# atxmega_e5.net
KiCad netlist of a schematic drawn in EAGLE
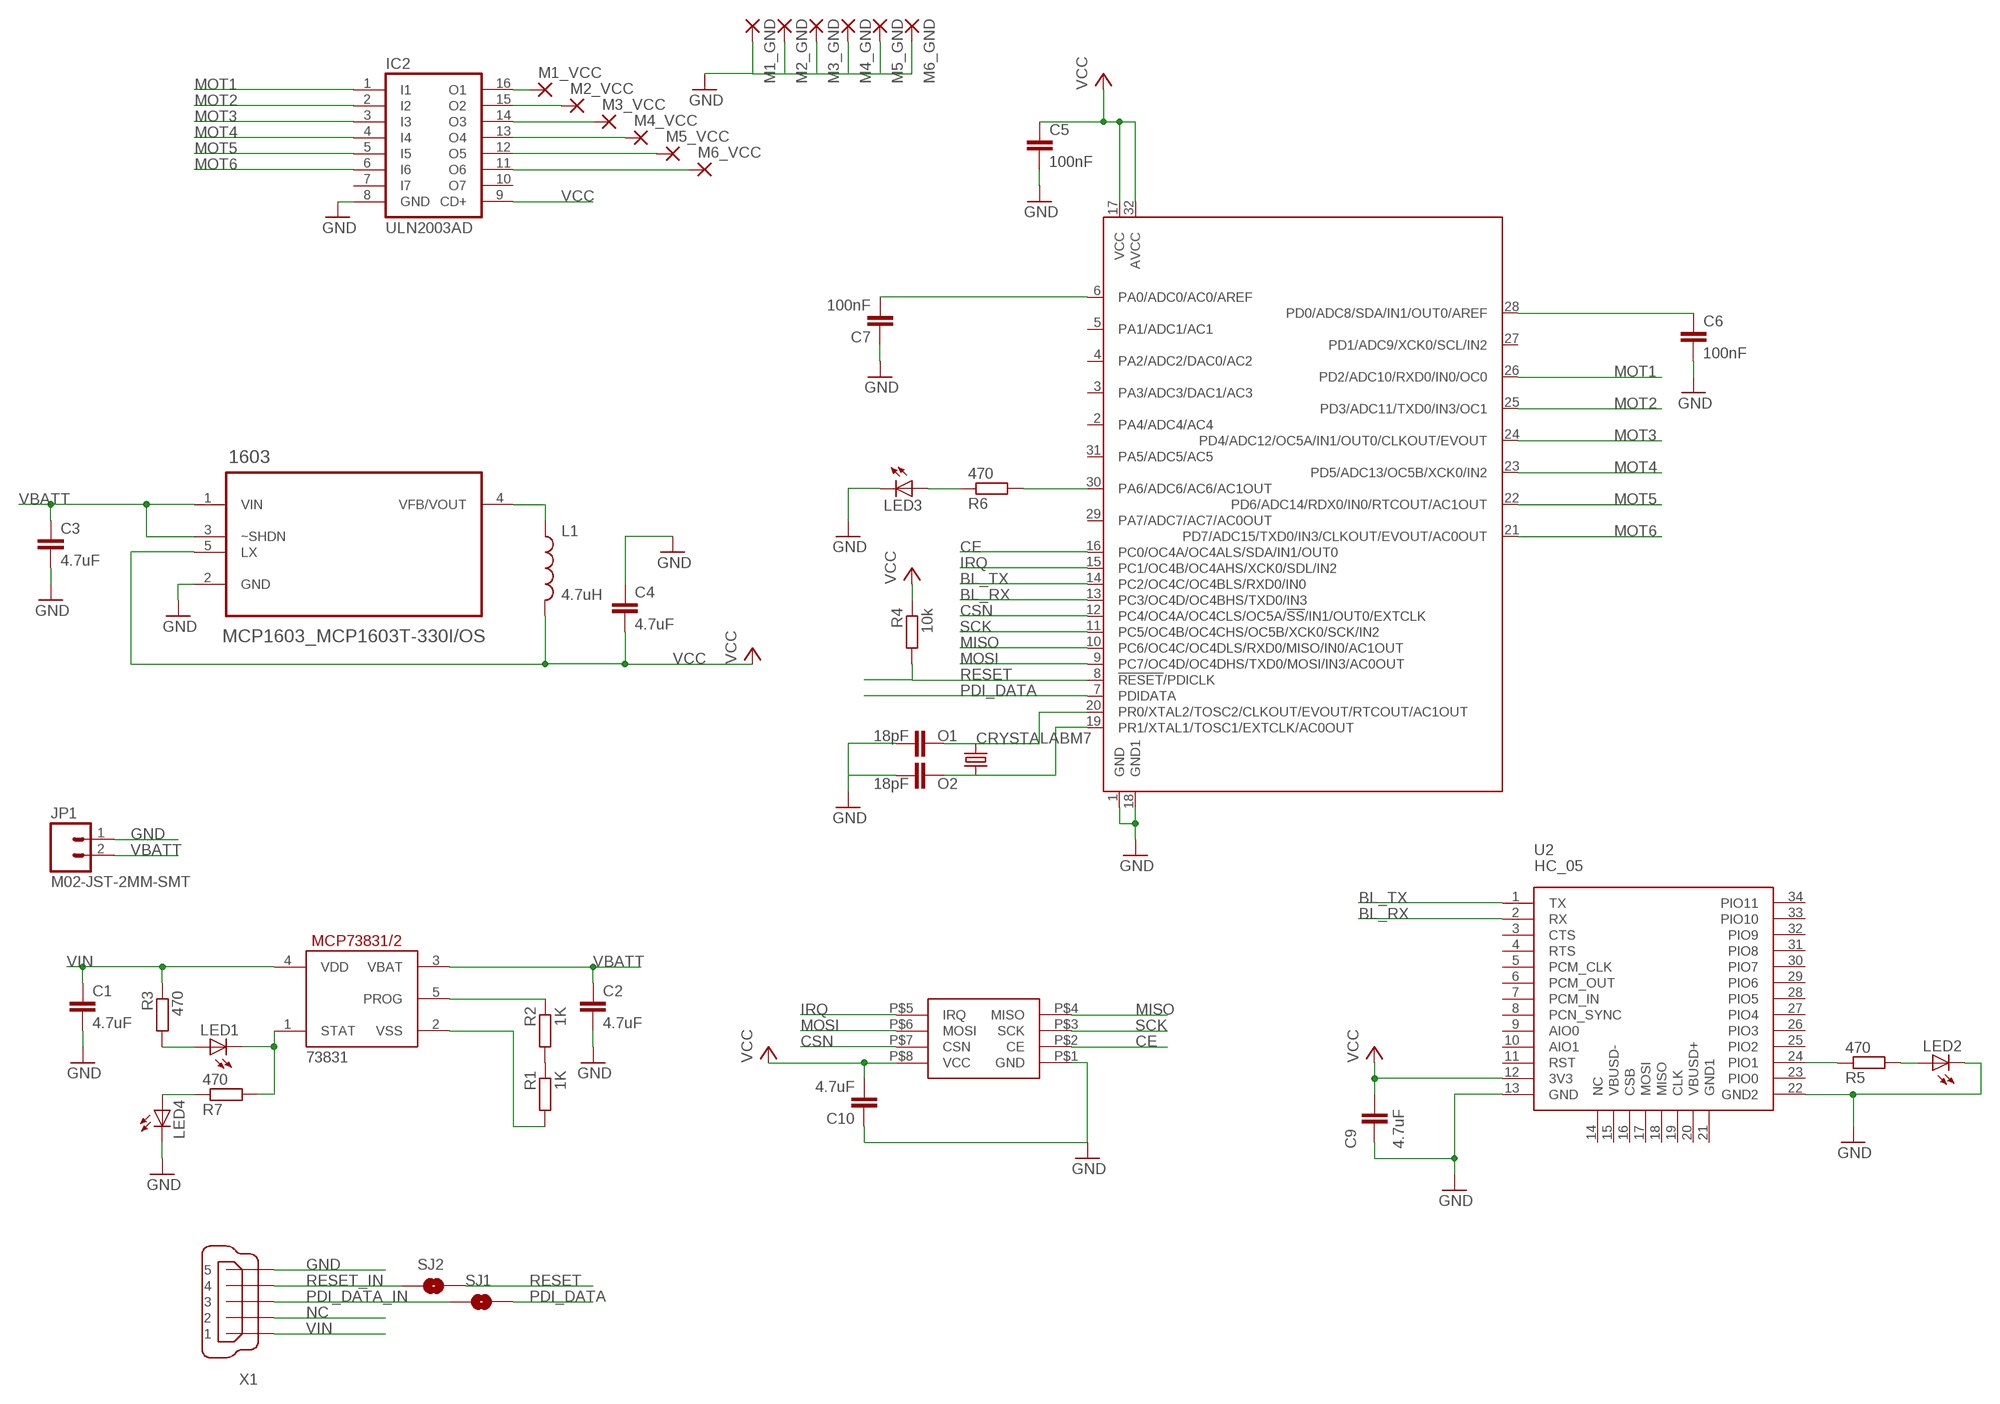
[diagram p0: schematic, sheet 1]

(export (version "E")
  (design (tool "Eeschema 10.0.6"))
  (components
    (comp (ref "1603")
      (value "MCP1603_MCP1603T-330I/OS")
      (footprint "eagle-import:MCP1603_SOT95P280X110-5N")
      (fields (field (name "MPN") "MCP1603T-330I/OS"))
      (libsource (lib "eagle-import") (part "MCP1603_MCP1603T-330I/OS"))
    )
    (comp (ref "73831")
      (value "MCP73831/OT")
      (footprint "eagle-import:SOT23-5L")
      (libsource (lib "eagle-import") (part "MCP73831/OT"))
    )
    (comp (ref "C1")
      (value "4.7uF")
      (footprint "eagle-import:C0603K")
      (libsource (lib "eagle-import") (part "C-EUC0603K"))
    )
    (comp (ref "C2")
      (value "4.7uF")
      (footprint "eagle-import:C0603K")
      (libsource (lib "eagle-import") (part "C-EUC0603K"))
    )
    (comp (ref "C3")
      (value "4.7uF")
      (footprint "eagle-import:C0603K")
      (libsource (lib "eagle-import") (part "C-EUC0603K"))
    )
    (comp (ref "C4")
      (value "4.7uF")
      (footprint "eagle-import:C0603K")
      (libsource (lib "eagle-import") (part "C-EUC0603K"))
    )
    (comp (ref "C5")
      (value "100nF")
      (footprint "eagle-import:C0603K")
      (libsource (lib "eagle-import") (part "C-EUC0603K"))
    )
    (comp (ref "C6")
      (value "100nF")
      (footprint "eagle-import:C0603K")
      (libsource (lib "eagle-import") (part "C-EUC0603K"))
    )
    (comp (ref "C7")
      (value "100nF")
      (footprint "eagle-import:C0603K")
      (libsource (lib "eagle-import") (part "C-EUC0603K"))
    )
    (comp (ref "C9")
      (value "4.7uF")
      (footprint "eagle-import:C0603K")
      (libsource (lib "eagle-import") (part "C-EUC0603K"))
    )
    (comp (ref "C10")
      (value "4.7uF")
      (footprint "eagle-import:C0603K")
      (libsource (lib "eagle-import") (part "C-EUC0603K"))
    )
    (comp (ref "IC2")
      (value "ULN2003AD")
      (footprint "eagle-import:SO16")
      (libsource (lib "eagle-import") (part "ULN2003AD"))
    )
    (comp (ref "JP1")
      (value "M02-JST-2MM-SMT")
      (footprint "eagle-import:JST-2-SMD")
      (libsource (lib "eagle-import") (part "M02-JST-2MM-SMT"))
    )
    (comp (ref "L1")
      (value "4.7uH")
      (footprint "eagle-import:1007")
      (libsource (lib "eagle-import") (part "INDUCTOR1007"))
    )
    (comp (ref "LED1")
      (value "LED0805LED")
      (footprint "eagle-import:0805LED")
      (libsource (lib "eagle-import") (part "LED0805LED"))
    )
    (comp (ref "LED2")
      (value "LED0805LED")
      (footprint "eagle-import:0805LED")
      (libsource (lib "eagle-import") (part "LED0805LED"))
    )
    (comp (ref "LED3")
      (value "LED0805LED")
      (footprint "eagle-import:0805LED")
      (libsource (lib "eagle-import") (part "LED0805LED"))
    )
    (comp (ref "LED4")
      (value "LED0805LED")
      (footprint "eagle-import:0805LED")
      (libsource (lib "eagle-import") (part "LED0805LED"))
    )
    (comp (ref "M1_GND")
      (value "WIREPAD2,15/1,0")
      (footprint "eagle-import:2,15_1,0")
      (libsource (lib "eagle-import") (part "WIREPAD2,15/1,0"))
    )
    (comp (ref "M1_VCC")
      (value "WIREPAD2,15/1,0")
      (footprint "eagle-import:2,15_1,0")
      (libsource (lib "eagle-import") (part "WIREPAD2,15/1,0"))
    )
    (comp (ref "M2_GND")
      (value "WIREPAD2,15/1,0")
      (footprint "eagle-import:2,15_1,0")
      (libsource (lib "eagle-import") (part "WIREPAD2,15/1,0"))
    )
    (comp (ref "M2_VCC")
      (value "WIREPAD2,15/1,0")
      (footprint "eagle-import:2,15_1,0")
      (libsource (lib "eagle-import") (part "WIREPAD2,15/1,0"))
    )
    (comp (ref "M3_GND")
      (value "WIREPAD2,15/1,0")
      (footprint "eagle-import:2,15_1,0")
      (libsource (lib "eagle-import") (part "WIREPAD2,15/1,0"))
    )
    (comp (ref "M3_VCC")
      (value "WIREPAD2,15/1,0")
      (footprint "eagle-import:2,15_1,0")
      (libsource (lib "eagle-import") (part "WIREPAD2,15/1,0"))
    )
    (comp (ref "M4_GND")
      (value "WIREPAD2,15/1,0")
      (footprint "eagle-import:2,15_1,0")
      (libsource (lib "eagle-import") (part "WIREPAD2,15/1,0"))
    )
    (comp (ref "M4_VCC")
      (value "WIREPAD2,15/1,0")
      (footprint "eagle-import:2,15_1,0")
      (libsource (lib "eagle-import") (part "WIREPAD2,15/1,0"))
    )
    (comp (ref "M5_GND")
      (value "WIREPAD2,15/1,0")
      (footprint "eagle-import:2,15_1,0")
      (libsource (lib "eagle-import") (part "WIREPAD2,15/1,0"))
    )
    (comp (ref "M5_VCC")
      (value "WIREPAD2,15/1,0")
      (footprint "eagle-import:2,15_1,0")
      (libsource (lib "eagle-import") (part "WIREPAD2,15/1,0"))
    )
    (comp (ref "M6_GND")
      (value "WIREPAD2,15/1,0")
      (footprint "eagle-import:2,15_1,0")
      (libsource (lib "eagle-import") (part "WIREPAD2,15/1,0"))
    )
    (comp (ref "M6_VCC")
      (value "WIREPAD2,15/1,0")
      (footprint "eagle-import:2,15_1,0")
      (libsource (lib "eagle-import") (part "WIREPAD2,15/1,0"))
    )
    (comp (ref "O1")
      (value "18pF")
      (footprint "eagle-import:C0603K")
      (libsource (lib "eagle-import") (part "C-EUC0603K"))
    )
    (comp (ref "O2")
      (value "18pF")
      (footprint "eagle-import:C0603K")
      (libsource (lib "eagle-import") (part "C-EUC0603K"))
    )
    (comp (ref "R1")
      (value "1K")
      (footprint "eagle-import:R0603")
      (libsource (lib "eagle-import") (part "R-EU_R0603"))
    )
    (comp (ref "R2")
      (value "1K")
      (footprint "eagle-import:R0603")
      (libsource (lib "eagle-import") (part "R-EU_R0603"))
    )
    (comp (ref "R3")
      (value "470")
      (footprint "eagle-import:R0603")
      (libsource (lib "eagle-import") (part "R-EU_R0603"))
    )
    (comp (ref "R4")
      (value "10k")
      (footprint "eagle-import:R0603")
      (libsource (lib "eagle-import") (part "R-EU_R0603"))
    )
    (comp (ref "R5")
      (value "470")
      (footprint "eagle-import:R0603")
      (libsource (lib "eagle-import") (part "R-EU_R0603"))
    )
    (comp (ref "R6")
      (value "470")
      (footprint "eagle-import:R0603")
      (libsource (lib "eagle-import") (part "R-EU_R0603"))
    )
    (comp (ref "R7")
      (value "470")
      (footprint "eagle-import:R0603")
      (libsource (lib "eagle-import") (part "R-EU_R0603"))
    )
    (comp (ref "SJ1")
      (value "SOLDERJUMPERNO")
      (footprint "eagle-import:SJ_2S-NO")
      (libsource (lib "eagle-import") (part "SOLDERJUMPERNO"))
    )
    (comp (ref "SJ2")
      (value "SOLDERJUMPERNO")
      (footprint "eagle-import:SJ_2S-NO")
      (libsource (lib "eagle-import") (part "SOLDERJUMPERNO"))
    )
    (comp (ref "U$1")
      (value "CRYSTALABM7")
      (footprint "eagle-import:ABM7")
      (libsource (lib "eagle-import") (part "CRYSTALABM7"))
    )
    (comp (ref "U$2")
      (value "NRF24L01+")
      (footprint "eagle-import:NRF24L01+")
      (libsource (lib "eagle-import") (part "NRF24L01+"))
    )
    (comp (ref "U1")
      (value "ATXMEGAE5AU")
      (footprint "eagle-import:TQFP32")
      (libsource (lib "eagle-import") (part "ATXMEGAE5AU"))
    )
    (comp (ref "U2")
      (value "HC_05")
      (footprint "eagle-import:BLUETOOTH_SMD")
      (libsource (lib "eagle-import") (part "HC_05"))
    )
    (comp (ref "X1")
      (value "MINI-USB-32005-201")
      (footprint "eagle-import:32005-201")
      (libsource (lib "eagle-import") (part "MINI-USB-32005-201"))
    )
  )
  (nets
    (net (code "1") (name "/BL_RX") (class "Default")
      (node (ref "U1") (pin "13") (pinfunction "PC3/OC4D/OC4BHS/TXD0/IN3_13") (pintype "bidirectional"))
      (node (ref "U2") (pin "2") (pinfunction "RX_2") (pintype "bidirectional"))
    )
    (net (code "2") (name "/BL_TX") (class "Default")
      (node (ref "U1") (pin "14") (pinfunction "PC2/OC4C/OC4BLS/RXD0/IN0_14") (pintype "bidirectional"))
      (node (ref "U2") (pin "1") (pinfunction "TX_1") (pintype "bidirectional"))
    )
    (net (code "3") (name "/CE") (class "Default")
      (node (ref "U$2") (pin "P$2") (pinfunction "CE_P$2") (pintype "bidirectional"))
      (node (ref "U1") (pin "16") (pinfunction "PC0/OC4A/OC4ALS/SDA/IN1/OUT0_16") (pintype "bidirectional"))
    )
    (net (code "4") (name "/CSN") (class "Default")
      (node (ref "U$2") (pin "P$7") (pinfunction "CSN_P$7") (pintype "bidirectional"))
      (node (ref "U1") (pin "12") (pinfunction "PC4/OC4A/OC4CLS/OC5A/~{SS}/IN1/OUT0/EXTCLK_12") (pintype "bidirectional"))
    )
    (net (code "5") (name "/IRQ") (class "Default")
      (node (ref "U$2") (pin "P$5") (pinfunction "IRQ_P$5") (pintype "bidirectional"))
      (node (ref "U1") (pin "15") (pinfunction "PC1/OC4B/OC4AHS/XCK0/SDL/IN2_15") (pintype "bidirectional"))
    )
    (net (code "6") (name "/MISO") (class "Default")
      (node (ref "U$2") (pin "P$4") (pinfunction "MISO_P$4") (pintype "bidirectional"))
      (node (ref "U1") (pin "10") (pinfunction "PC6/OC4C/OC4DLS/RXD0/MISO/IN0/AC1OUT_10") (pintype "bidirectional"))
    )
    (net (code "7") (name "/MOSI") (class "Default")
      (node (ref "U$2") (pin "P$6") (pinfunction "MOSI_P$6") (pintype "bidirectional"))
      (node (ref "U1") (pin "9") (pinfunction "PC7/OC4D/OC4DHS/TXD0/MOSI/IN3/AC0OUT_9") (pintype "bidirectional"))
    )
    (net (code "8") (name "/MOT1") (class "Default")
      (node (ref "IC2") (pin "1") (pinfunction "I1_1") (pintype "input"))
      (node (ref "U1") (pin "26") (pinfunction "PD2/ADC10/RXD0/IN0/OC0_26") (pintype "bidirectional"))
    )
    (net (code "9") (name "/MOT2") (class "Default")
      (node (ref "IC2") (pin "2") (pinfunction "I2_2") (pintype "input"))
      (node (ref "U1") (pin "25") (pinfunction "PD3/ADC11/TXD0/IN3/OC1_25") (pintype "bidirectional"))
    )
    (net (code "10") (name "/MOT3") (class "Default")
      (node (ref "IC2") (pin "3") (pinfunction "I3_3") (pintype "input"))
      (node (ref "U1") (pin "24") (pinfunction "PD4/ADC12/OC5A/IN1/OUT0/CLKOUT/EVOUT_24") (pintype "bidirectional"))
    )
    (net (code "11") (name "/MOT4") (class "Default")
      (node (ref "IC2") (pin "4") (pinfunction "I4_4") (pintype "input"))
      (node (ref "U1") (pin "23") (pinfunction "PD5/ADC13/OC5B/XCK0/IN2_23") (pintype "bidirectional"))
    )
    (net (code "12") (name "/MOT5") (class "Default")
      (node (ref "IC2") (pin "5") (pinfunction "I5_5") (pintype "input"))
      (node (ref "U1") (pin "22") (pinfunction "PD6/ADC14/RDX0/IN0/RTCOUT/AC1OUT_22") (pintype "bidirectional"))
    )
    (net (code "13") (name "/MOT6") (class "Default")
      (node (ref "IC2") (pin "6") (pinfunction "I6_6") (pintype "input"))
      (node (ref "U1") (pin "21") (pinfunction "PD7/ADC15/TXD0/IN3/CLKOUT/EVOUT/AC0OUT_21") (pintype "bidirectional"))
    )
    (net (code "14") (name "/NC") (class "Default")
      (node (ref "X1") (pin "2") (pinfunction "2_2") (pintype "passive"))
    )
    (net (code "15") (name "/PDI_DATA") (class "Default")
      (node (ref "SJ1") (pin "2") (pinfunction "2_2") (pintype "passive"))
      (node (ref "U1") (pin "7") (pinfunction "PDIDATA_7") (pintype "bidirectional"))
    )
    (net (code "16") (name "/PDI_DATA_IN") (class "Default")
      (node (ref "SJ1") (pin "1") (pinfunction "1_1") (pintype "passive"))
      (node (ref "X1") (pin "3") (pinfunction "3_3") (pintype "passive"))
    )
    (net (code "17") (name "/RESET") (class "Default")
      (node (ref "R4") (pin "2") (pinfunction "2_2") (pintype "passive"))
      (node (ref "SJ2") (pin "2") (pinfunction "2_2") (pintype "passive"))
      (node (ref "U1") (pin "8") (pinfunction "~{RESET}/PDICLK_8") (pintype "bidirectional"))
    )
    (net (code "18") (name "/RESET_IN") (class "Default")
      (node (ref "SJ2") (pin "1") (pinfunction "1_1") (pintype "passive"))
      (node (ref "X1") (pin "4") (pinfunction "4_4") (pintype "passive"))
    )
    (net (code "19") (name "/SCK") (class "Default")
      (node (ref "U$2") (pin "P$3") (pinfunction "SCK_P$3") (pintype "bidirectional"))
      (node (ref "U1") (pin "11") (pinfunction "PC5/OC4B/OC4CHS/OC5B/XCK0/SCK/IN2_11") (pintype "bidirectional"))
    )
    (net (code "20") (name "/VBATT") (class "Default")
      (node (ref "1603") (pin "1") (pinfunction "VIN_1") (pintype "power_in"))
      (node (ref "1603") (pin "3") (pinfunction "~{SHDN}_3") (pintype "input"))
      (node (ref "73831") (pin "3") (pinfunction "VBAT_3") (pintype "bidirectional"))
      (node (ref "C2") (pin "1") (pinfunction "1_1") (pintype "passive"))
      (node (ref "C3") (pin "1") (pinfunction "1_1") (pintype "passive"))
      (node (ref "JP1") (pin "2") (pinfunction "1_2") (pintype "passive"))
    )
    (net (code "21") (name "/VIN") (class "Default")
      (node (ref "73831") (pin "4") (pinfunction "VDD_4") (pintype "power_in"))
      (node (ref "C1") (pin "1") (pinfunction "1_1") (pintype "passive"))
      (node (ref "R3") (pin "1") (pinfunction "1_1") (pintype "passive"))
      (node (ref "X1") (pin "1") (pinfunction "1_1") (pintype "passive"))
    )
    (net (code "22") (name "GND") (class "Default")
      (node (ref "1603") (pin "2") (pinfunction "GND_2") (pintype "passive"))
      (node (ref "C1") (pin "2") (pinfunction "2_2") (pintype "passive"))
      (node (ref "C10") (pin "1") (pinfunction "1_1") (pintype "passive"))
      (node (ref "C2") (pin "2") (pinfunction "2_2") (pintype "passive"))
      (node (ref "C3") (pin "2") (pinfunction "2_2") (pintype "passive"))
      (node (ref "C4") (pin "1") (pinfunction "1_1") (pintype "passive"))
      (node (ref "C5") (pin "2") (pinfunction "2_2") (pintype "passive"))
      (node (ref "C6") (pin "2") (pinfunction "2_2") (pintype "passive"))
      (node (ref "C7") (pin "1") (pinfunction "1_1") (pintype "passive"))
      (node (ref "C9") (pin "2") (pinfunction "2_2") (pintype "passive"))
      (node (ref "IC2") (pin "8") (pinfunction "GND_8") (pintype "power_in"))
      (node (ref "JP1") (pin "1") (pinfunction "2_1") (pintype "passive"))
      (node (ref "LED2") (pin "C") (pinfunction "C_C") (pintype "passive"))
      (node (ref "LED3") (pin "C") (pinfunction "C_C") (pintype "passive"))
      (node (ref "LED4") (pin "C") (pinfunction "C_C") (pintype "passive"))
      (node (ref "M1_GND") (pin "1") (pinfunction "P_1") (pintype "passive"))
      (node (ref "M2_GND") (pin "1") (pinfunction "P_1") (pintype "passive"))
      (node (ref "M3_GND") (pin "1") (pinfunction "P_1") (pintype "passive"))
      (node (ref "M4_GND") (pin "1") (pinfunction "P_1") (pintype "passive"))
      (node (ref "M5_GND") (pin "1") (pinfunction "P_1") (pintype "passive"))
      (node (ref "M6_GND") (pin "1") (pinfunction "P_1") (pintype "passive"))
      (node (ref "O1") (pin "2") (pinfunction "2_2") (pintype "passive"))
      (node (ref "O2") (pin "2") (pinfunction "2_2") (pintype "passive"))
      (node (ref "U$2") (pin "P$1") (pinfunction "GND_P$1") (pintype "power_in"))
      (node (ref "U1") (pin "1") (pinfunction "GND_1") (pintype "bidirectional"))
      (node (ref "U1") (pin "18") (pinfunction "GND1_18") (pintype "bidirectional"))
      (node (ref "U2") (pin "13") (pinfunction "GND_13") (pintype "bidirectional"))
      (node (ref "U2") (pin "22") (pinfunction "GND2_22") (pintype "bidirectional"))
      (node (ref "X1") (pin "5") (pinfunction "5_5") (pintype "passive"))
    )
    (net (code "23") (name "Net-(1603-VFB{slash}VOUT)") (class "Default")
      (node (ref "1603") (pin "4") (pinfunction "VFB/VOUT_4") (pintype "output"))
      (node (ref "L1") (pin "1") (pinfunction "1_1") (pintype "passive"))
    )
    (net (code "24") (name "Net-(73831-PROG)") (class "Default")
      (node (ref "73831") (pin "5") (pinfunction "PROG_5") (pintype "input"))
      (node (ref "R2") (pin "1") (pinfunction "1_1") (pintype "passive"))
    )
    (net (code "25") (name "Net-(73831-STAT)") (class "Default")
      (node (ref "73831") (pin "1") (pinfunction "STAT_1") (pintype "output"))
      (node (ref "LED1") (pin "C") (pinfunction "C_C") (pintype "passive"))
      (node (ref "R7") (pin "2") (pinfunction "2_2") (pintype "passive"))
    )
    (net (code "26") (name "Net-(73831-VSS)") (class "Default")
      (node (ref "73831") (pin "2") (pinfunction "VSS_2") (pintype "power_in"))
      (node (ref "R1") (pin "2") (pinfunction "2_2") (pintype "passive"))
    )
    (net (code "27") (name "Net-(IC2-O1)") (class "Default")
      (node (ref "IC2") (pin "16") (pinfunction "O1_16") (pintype "open_collector"))
      (node (ref "M1_VCC") (pin "1") (pinfunction "P_1") (pintype "passive"))
    )
    (net (code "28") (name "Net-(IC2-O2)") (class "Default")
      (node (ref "IC2") (pin "15") (pinfunction "O2_15") (pintype "open_collector"))
      (node (ref "M2_VCC") (pin "1") (pinfunction "P_1") (pintype "passive"))
    )
    (net (code "29") (name "Net-(IC2-O3)") (class "Default")
      (node (ref "IC2") (pin "14") (pinfunction "O3_14") (pintype "open_collector"))
      (node (ref "M3_VCC") (pin "1") (pinfunction "P_1") (pintype "passive"))
    )
    (net (code "30") (name "Net-(IC2-O4)") (class "Default")
      (node (ref "IC2") (pin "13") (pinfunction "O4_13") (pintype "open_collector"))
      (node (ref "M4_VCC") (pin "1") (pinfunction "P_1") (pintype "passive"))
    )
    (net (code "31") (name "Net-(IC2-O5)") (class "Default")
      (node (ref "IC2") (pin "12") (pinfunction "O5_12") (pintype "open_collector"))
      (node (ref "M5_VCC") (pin "1") (pinfunction "P_1") (pintype "passive"))
    )
    (net (code "32") (name "Net-(IC2-O6)") (class "Default")
      (node (ref "IC2") (pin "11") (pinfunction "O6_11") (pintype "open_collector"))
      (node (ref "M6_VCC") (pin "1") (pinfunction "P_1") (pintype "passive"))
    )
    (net (code "33") (name "Net-(LED1-PadA)") (class "Default")
      (node (ref "LED1") (pin "A") (pinfunction "A_A") (pintype "passive"))
      (node (ref "R3") (pin "2") (pinfunction "2_2") (pintype "passive"))
    )
    (net (code "34") (name "Net-(LED2-PadA)") (class "Default")
      (node (ref "LED2") (pin "A") (pinfunction "A_A") (pintype "passive"))
      (node (ref "R5") (pin "2") (pinfunction "2_2") (pintype "passive"))
    )
    (net (code "35") (name "Net-(LED3-PadA)") (class "Default")
      (node (ref "LED3") (pin "A") (pinfunction "A_A") (pintype "passive"))
      (node (ref "R6") (pin "1") (pinfunction "1_1") (pintype "passive"))
    )
    (net (code "36") (name "Net-(LED4-PadA)") (class "Default")
      (node (ref "LED4") (pin "A") (pinfunction "A_A") (pintype "passive"))
      (node (ref "R7") (pin "1") (pinfunction "1_1") (pintype "passive"))
    )
    (net (code "37") (name "Net-(R1-Pad1)") (class "Default")
      (node (ref "R1") (pin "1") (pinfunction "1_1") (pintype "passive"))
      (node (ref "R2") (pin "2") (pinfunction "2_2") (pintype "passive"))
    )
    (net (code "38") (name "Net-(U$1-1)") (class "Default")
      (node (ref "O2") (pin "1") (pinfunction "1_1") (pintype "passive"))
      (node (ref "U$1") (pin "P$1") (pinfunction "1_P$1") (pintype "passive"))
      (node (ref "U1") (pin "19") (pinfunction "PR1/XTAL1/TOSC1/EXTCLK/AC0OUT_19") (pintype "bidirectional"))
    )
    (net (code "39") (name "Net-(U$1-2)") (class "Default")
      (node (ref "O1") (pin "1") (pinfunction "1_1") (pintype "passive"))
      (node (ref "U$1") (pin "P$2") (pinfunction "2_P$2") (pintype "passive"))
      (node (ref "U1") (pin "20") (pinfunction "PR0/XTAL2/TOSC2/CLKOUT/EVOUT/RTCOUT/AC1OUT_20") (pintype "bidirectional"))
    )
    (net (code "40") (name "Net-(U1-PA0{slash}ADC0{slash}AC0{slash}AREF)") (class "Default")
      (node (ref "C7") (pin "2") (pinfunction "2_2") (pintype "passive"))
      (node (ref "U1") (pin "6") (pinfunction "PA0/ADC0/AC0/AREF_6") (pintype "bidirectional"))
    )
    (net (code "41") (name "Net-(U1-PA6{slash}ADC6{slash}AC6{slash}AC1OUT)") (class "Default")
      (node (ref "R6") (pin "2") (pinfunction "2_2") (pintype "passive"))
      (node (ref "U1") (pin "30") (pinfunction "PA6/ADC6/AC6/AC1OUT_30") (pintype "bidirectional"))
    )
    (net (code "42") (name "Net-(U1-PD0{slash}ADC8{slash}SDA{slash}IN1{slash}OUT0{slash}AREF)") (class "Default")
      (node (ref "C6") (pin "1") (pinfunction "1_1") (pintype "passive"))
      (node (ref "U1") (pin "28") (pinfunction "PD0/ADC8/SDA/IN1/OUT0/AREF_28") (pintype "bidirectional"))
    )
    (net (code "43") (name "Net-(U2-PIO1)") (class "Default")
      (node (ref "R5") (pin "1") (pinfunction "1_1") (pintype "passive"))
      (node (ref "U2") (pin "24") (pinfunction "PIO1_24") (pintype "bidirectional"))
    )
    (net (code "44") (name "VCC") (class "Default")
      (node (ref "1603") (pin "5") (pinfunction "LX_5") (pintype "input"))
      (node (ref "C10") (pin "2") (pinfunction "2_2") (pintype "passive"))
      (node (ref "C4") (pin "2") (pinfunction "2_2") (pintype "passive"))
      (node (ref "C5") (pin "1") (pinfunction "1_1") (pintype "passive"))
      (node (ref "C9") (pin "1") (pinfunction "1_1") (pintype "passive"))
      (node (ref "IC2") (pin "9") (pinfunction "CD+_9") (pintype "passive"))
      (node (ref "L1") (pin "2") (pinfunction "2_2") (pintype "passive"))
      (node (ref "R4") (pin "1") (pinfunction "1_1") (pintype "passive"))
      (node (ref "U$2") (pin "P$8") (pinfunction "VCC_P$8") (pintype "power_in"))
      (node (ref "U1") (pin "17") (pinfunction "VCC_17") (pintype "bidirectional"))
      (node (ref "U1") (pin "32") (pinfunction "AVCC_32") (pintype "bidirectional"))
      (node (ref "U2") (pin "12") (pinfunction "3V3_12") (pintype "bidirectional"))
    )
    (net (code "45") (name "unconnected-(IC2-I7-Pad7)") (class "Default")
      (node (ref "IC2") (pin "7") (pinfunction "I7_7") (pintype "input"))
    )
    (net (code "46") (name "unconnected-(IC2-O7-Pad10)") (class "Default")
      (node (ref "IC2") (pin "10") (pinfunction "O7_10") (pintype "open_collector"))
    )
    (net (code "47") (name "unconnected-(U1-PA1{slash}ADC1{slash}AC1-Pad5)") (class "Default")
      (node (ref "U1") (pin "5") (pinfunction "PA1/ADC1/AC1_5") (pintype "bidirectional"))
    )
    (net (code "48") (name "unconnected-(U1-PA2{slash}ADC2{slash}DAC0{slash}AC2-Pad4)") (class "Default")
      (node (ref "U1") (pin "4") (pinfunction "PA2/ADC2/DAC0/AC2_4") (pintype "bidirectional"))
    )
    (net (code "49") (name "unconnected-(U1-PA3{slash}ADC3{slash}DAC1{slash}AC3-Pad3)") (class "Default")
      (node (ref "U1") (pin "3") (pinfunction "PA3/ADC3/DAC1/AC3_3") (pintype "bidirectional"))
    )
    (net (code "50") (name "unconnected-(U1-PA4{slash}ADC4{slash}AC4-Pad2)") (class "Default")
      (node (ref "U1") (pin "2") (pinfunction "PA4/ADC4/AC4_2") (pintype "bidirectional"))
    )
    (net (code "51") (name "unconnected-(U1-PA5{slash}ADC5{slash}AC5-Pad31)") (class "Default")
      (node (ref "U1") (pin "31") (pinfunction "PA5/ADC5/AC5_31") (pintype "bidirectional"))
    )
    (net (code "52") (name "unconnected-(U1-PA7{slash}ADC7{slash}AC7{slash}AC0OUT-Pad29)") (class "Default")
      (node (ref "U1") (pin "29") (pinfunction "PA7/ADC7/AC7/AC0OUT_29") (pintype "bidirectional"))
    )
    (net (code "53") (name "unconnected-(U1-PD1{slash}ADC9{slash}XCK0{slash}SCL{slash}IN2-Pad27)") (class "Default")
      (node (ref "U1") (pin "27") (pinfunction "PD1/ADC9/XCK0/SCL/IN2_27") (pintype "bidirectional"))
    )
    (net (code "54") (name "unconnected-(U2-AIO0-Pad9)") (class "Default")
      (node (ref "U2") (pin "9") (pinfunction "AIO0_9") (pintype "bidirectional"))
    )
    (net (code "55") (name "unconnected-(U2-AIO1-Pad10)") (class "Default")
      (node (ref "U2") (pin "10") (pinfunction "AIO1_10") (pintype "bidirectional"))
    )
    (net (code "56") (name "unconnected-(U2-CLK-Pad19)") (class "Default")
      (node (ref "U2") (pin "19") (pinfunction "CLK_19") (pintype "bidirectional"))
    )
    (net (code "57") (name "unconnected-(U2-CSB-Pad16)") (class "Default")
      (node (ref "U2") (pin "16") (pinfunction "CSB_16") (pintype "bidirectional"))
    )
    (net (code "58") (name "unconnected-(U2-CTS-Pad3)") (class "Default")
      (node (ref "U2") (pin "3") (pinfunction "CTS_3") (pintype "bidirectional"))
    )
    (net (code "59") (name "unconnected-(U2-GND1-Pad21)") (class "Default")
      (node (ref "U2") (pin "21") (pinfunction "GND1_21") (pintype "bidirectional"))
    )
    (net (code "60") (name "unconnected-(U2-MISO-Pad18)") (class "Default")
      (node (ref "U2") (pin "18") (pinfunction "MISO_18") (pintype "bidirectional"))
    )
    (net (code "61") (name "unconnected-(U2-MOSI-Pad17)") (class "Default")
      (node (ref "U2") (pin "17") (pinfunction "MOSI_17") (pintype "bidirectional"))
    )
    (net (code "62") (name "unconnected-(U2-NC-Pad14)") (class "Default")
      (node (ref "U2") (pin "14") (pinfunction "NC_14") (pintype "bidirectional"))
    )
    (net (code "63") (name "unconnected-(U2-PCM_CLK-Pad5)") (class "Default")
      (node (ref "U2") (pin "5") (pinfunction "PCM_CLK_5") (pintype "bidirectional"))
    )
    (net (code "64") (name "unconnected-(U2-PCM_IN-Pad7)") (class "Default")
      (node (ref "U2") (pin "7") (pinfunction "PCM_IN_7") (pintype "bidirectional"))
    )
    (net (code "65") (name "unconnected-(U2-PCM_OUT-Pad6)") (class "Default")
      (node (ref "U2") (pin "6") (pinfunction "PCM_OUT_6") (pintype "bidirectional"))
    )
    (net (code "66") (name "unconnected-(U2-PCN_SYNC-Pad8)") (class "Default")
      (node (ref "U2") (pin "8") (pinfunction "PCN_SYNC_8") (pintype "bidirectional"))
    )
    (net (code "67") (name "unconnected-(U2-PIO0-Pad23)") (class "Default")
      (node (ref "U2") (pin "23") (pinfunction "PIO0_23") (pintype "bidirectional"))
    )
    (net (code "68") (name "unconnected-(U2-PIO2-Pad25)") (class "Default")
      (node (ref "U2") (pin "25") (pinfunction "PIO2_25") (pintype "bidirectional"))
    )
    (net (code "69") (name "unconnected-(U2-PIO3-Pad26)") (class "Default")
      (node (ref "U2") (pin "26") (pinfunction "PIO3_26") (pintype "bidirectional"))
    )
    (net (code "70") (name "unconnected-(U2-PIO4-Pad27)") (class "Default")
      (node (ref "U2") (pin "27") (pinfunction "PIO4_27") (pintype "bidirectional"))
    )
    (net (code "71") (name "unconnected-(U2-PIO5-Pad28)") (class "Default")
      (node (ref "U2") (pin "28") (pinfunction "PIO5_28") (pintype "bidirectional"))
    )
    (net (code "72") (name "unconnected-(U2-PIO6-Pad29)") (class "Default")
      (node (ref "U2") (pin "29") (pinfunction "PIO6_29") (pintype "bidirectional"))
    )
    (net (code "73") (name "unconnected-(U2-PIO7-Pad30)") (class "Default")
      (node (ref "U2") (pin "30") (pinfunction "PIO7_30") (pintype "bidirectional"))
    )
    (net (code "74") (name "unconnected-(U2-PIO8-Pad31)") (class "Default")
      (node (ref "U2") (pin "31") (pinfunction "PIO8_31") (pintype "bidirectional"))
    )
    (net (code "75") (name "unconnected-(U2-PIO9-Pad32)") (class "Default")
      (node (ref "U2") (pin "32") (pinfunction "PIO9_32") (pintype "bidirectional"))
    )
    (net (code "76") (name "unconnected-(U2-PIO10-Pad33)") (class "Default")
      (node (ref "U2") (pin "33") (pinfunction "PIO10_33") (pintype "bidirectional"))
    )
    (net (code "77") (name "unconnected-(U2-PIO11-Pad34)") (class "Default")
      (node (ref "U2") (pin "34") (pinfunction "PIO11_34") (pintype "bidirectional"))
    )
    (net (code "78") (name "unconnected-(U2-RST-Pad11)") (class "Default")
      (node (ref "U2") (pin "11") (pinfunction "RST_11") (pintype "bidirectional"))
    )
    (net (code "79") (name "unconnected-(U2-RTS-Pad4)") (class "Default")
      (node (ref "U2") (pin "4") (pinfunction "RTS_4") (pintype "bidirectional"))
    )
    (net (code "80") (name "unconnected-(U2-VBUSD+-Pad20)") (class "Default")
      (node (ref "U2") (pin "20") (pinfunction "VBUSD+_20") (pintype "bidirectional"))
    )
    (net (code "81") (name "unconnected-(U2-VBUSD--Pad15)") (class "Default")
      (node (ref "U2") (pin "15") (pinfunction "VBUSD-_15") (pintype "bidirectional"))
    )
  )
)
